# Analog_amplifer_1.net
KiCad netlist of a schematic drawn in EAGLE
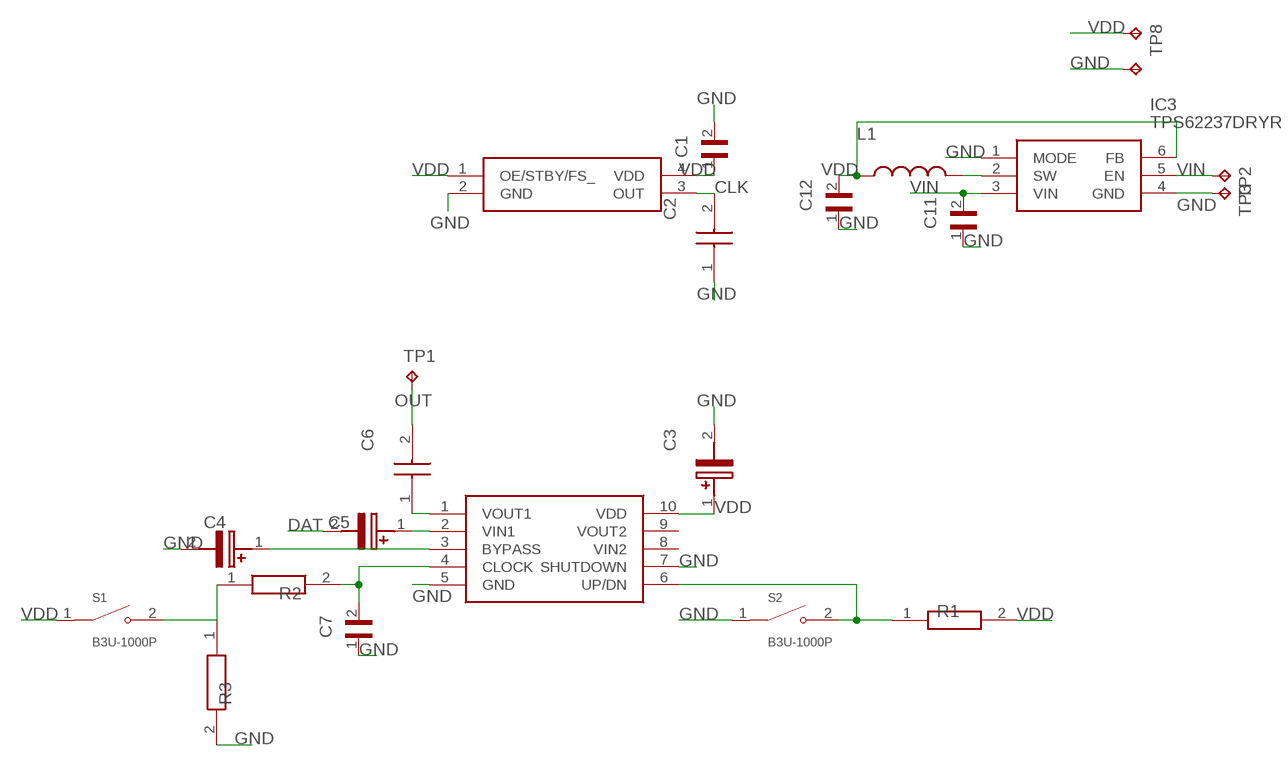
[diagram p0: schematic, sheet 1]
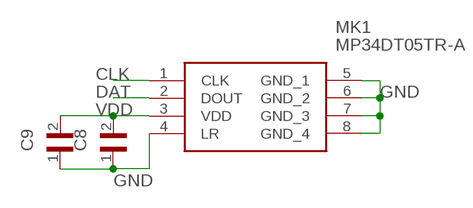
[diagram p1: schematic, sheet 2]

(export (version "E")
  (design (tool "Eeschema 10.0.6"))
  (components
    (comp (ref "C8")
      (value "JMK105C6105KV-F")
      (footprint "eagle-import:CAPC1005X55N")
      (fields (field (name "DIGI-KEY_PART_NUMBER") "587-3381-1-ND") (field (name "MF") "Taiyo Yuden"))
      (libsource (lib "eagle-import") (part "JMK105C6105KV-F"))
    )
    (comp (ref "C9")
      (value "GRM033C80J104KE15D")
      (footprint "eagle-import:CAPC0603X33N")
      (fields (field (name "DIGI-KEY_PART_NUMBER") "490-10390-1-ND") (field (name "MF") "Murata Electronics"))
      (libsource (lib "eagle-import") (part "GRM033C80J104KE15D"))
    )
    (comp (ref "MK1")
      (value "MP34DT05TR-A")
      (footprint "eagle-import:MP34DT05TRA")
      (fields (field (name "MOUSER_PART_NUMBER") "511-MP34DT05TR-A"))
      (libsource (lib "eagle-import") (part "MP34DT05TR-A"))
    )
    (comp (ref "C1")
      (value "GRM033C80J104KE15D")
      (footprint "eagle-import:CAPC0603X33N")
      (fields (field (name "DIGI-KEY_PART_NUMBER") "490-10390-1-ND") (field (name "MF") "Murata Electronics"))
      (libsource (lib "eagle-import") (part "GRM033C80J104KE15D"))
    )
    (comp (ref "C2")
      (value "GRM0115C1E5R0CE01L")
      (footprint "eagle-import:CAPC0201X14N")
      (fields (field (name "MOUSER_PART_NUMBER") "81-GRM0115C1E5RCE01L"))
      (libsource (lib "eagle-import") (part "GRM0115C1E5R0CE01L"))
    )
    (comp (ref "C3")
      (value "F380J105MUA")
      (footprint "eagle-import:CAPPC1106X60N")
      (fields (field (name "MOUSER_PART_NUMBER") "581-F380J105MUA"))
      (libsource (lib "eagle-import") (part "F380J105MUA"))
    )
    (comp (ref "C4")
      (value "F380J105MUA")
      (footprint "eagle-import:CAPPC1106X60N")
      (fields (field (name "MOUSER_PART_NUMBER") "581-F380J105MUA"))
      (libsource (lib "eagle-import") (part "F380J105MUA"))
    )
    (comp (ref "C5")
      (value "F380J105MUA")
      (footprint "eagle-import:CAPPC1106X60N")
      (fields (field (name "MOUSER_PART_NUMBER") "581-F380J105MUA"))
      (libsource (lib "eagle-import") (part "F380J105MUA"))
    )
    (comp (ref "C6")
      (value "GRM21BR60J107ME15L")
      (footprint "eagle-import:CAPC2012X145N")
      (fields (field (name "MOUSER_PART_NUMBER") "81-GRM21BR60J107ME5L"))
      (libsource (lib "eagle-import") (part "GRM21BR60J107ME15L"))
    )
    (comp (ref "C7")
      (value "GRM033C80J104KE15D")
      (footprint "eagle-import:CAPC0603X33N")
      (fields (field (name "DIGI-KEY_PART_NUMBER") "490-10390-1-ND") (field (name "MF") "Murata Electronics"))
      (libsource (lib "eagle-import") (part "GRM033C80J104KE15D"))
    )
    (comp (ref "C11")
      (value "GRM155R60J225KE95D")
      (footprint "eagle-import:CAPC1005X55N")
      (fields (field (name "DIGI-KEY_PART_NUMBER") "490-12532-1-ND") (field (name "MF") "Murata"))
      (libsource (lib "eagle-import") (part "GRM155R60J225KE95D"))
    )
    (comp (ref "C12")
      (value "GRM155R60J475ME47D")
      (footprint "eagle-import:CAPC1005X60N")
      (fields (field (name "DIGI-KEY_PART_NUMBER") "490-5915-1-ND") (field (name "MF") "Murata"))
      (libsource (lib "eagle-import") (part "GRM155R60J475ME47D"))
    )
    (comp (ref "IC1")
      (value "LM4811MM_NOPB")
      (footprint "eagle-import:SOP50P490X110-10N")
      (fields
        (field (name "ARROW_PART_NUMBER") "LM4811MM/NOPB")
        (field (name "MOUSER_PART_NUMBER") "926-LM4811MM/NOPB")
      )
      (libsource (lib "eagle-import") (part "LM4811MM_NOPB"))
    )
    (comp (ref "IC3")
      (value "TPS62237DRYR")
      (footprint "eagle-import:SON50P100X145X60-6N")
      (fields (field (name "MOUSER_PART_NUMBER") "595-TPS62237DRYR"))
      (libsource (lib "eagle-import") (part "TPS62237DRYR"))
    )
    (comp (ref "L1")
      (value "LQM21PN2R2MC0D")
      (footprint "eagle-import:INDC2012X55N")
      (fields (field (name "DIGI-KEY_PART_NUMBER") "490-4994-1-ND") (field (name "MF") "Murata"))
      (libsource (lib "eagle-import") (part "LQM21PN2R2MC0D"))
    )
    (comp (ref "R1")
      (value "RC0201FR-074K02L")
      (footprint "eagle-import:RESC0603X26N")
      (libsource (lib "eagle-import") (part "RC0201FR-074K02L"))
    )
    (comp (ref "R2")
      (value "RC0201FR-07100RL")
      (footprint "eagle-import:RESC0603X26N")
      (fields (field (name "MOUSER_PART_NUMBER") "603-RC0201FR-07100RL"))
      (libsource (lib "eagle-import") (part "RC0201FR-07100RL"))
    )
    (comp (ref "R3")
      (value "RC0201FR-07100RL")
      (footprint "eagle-import:RESC0603X26N")
      (fields (field (name "MOUSER_PART_NUMBER") "603-RC0201FR-07100RL"))
      (libsource (lib "eagle-import") (part "RC0201FR-07100RL"))
    )
    (comp (ref "S1")
      (value "B3U-1000P")
      (footprint "eagle-import:SW_B3U-1000P")
      (fields (field (name "DIGI-KEY_PART_NUMBER") "SW1020CT-ND") (field (name "MF") "Omron"))
      (libsource (lib "eagle-import") (part "B3U-1000P"))
    )
    (comp (ref "S2")
      (value "B3U-1000P")
      (footprint "eagle-import:SW_B3U-1000P")
      (fields (field (name "DIGI-KEY_PART_NUMBER") "SW1020CT-ND") (field (name "MF") "Omron"))
      (libsource (lib "eagle-import") (part "B3U-1000P"))
    )
    (comp (ref "TP1")
      (value "TPTP11R")
      (footprint "eagle-import:TP11R")
      (libsource (lib "eagle-import") (part "TPTP11R"))
    )
    (comp (ref "TP2")
      (value "TPTP11R")
      (footprint "eagle-import:TP11R")
      (libsource (lib "eagle-import") (part "TPTP11R"))
    )
    (comp (ref "TP3")
      (value "TPTP11R")
      (footprint "eagle-import:TP11R")
      (libsource (lib "eagle-import") (part "TPTP11R"))
    )
    (comp (ref "TP4")
      (value "TPTP11R")
      (footprint "eagle-import:TP11R")
      (libsource (lib "eagle-import") (part "TPTP11R"))
    )
    (comp (ref "TP8")
      (value "TPTP11R")
      (footprint "eagle-import:TP11R")
      (libsource (lib "eagle-import") (part "TPTP11R"))
    )
    (comp (ref "Y1")
      (value "DSC6053CE2A-003.0720")
      (footprint "eagle-import:DSC6053CE2A0030720")
      (libsource (lib "eagle-import") (part "DSC6053CE2A-003.0720"))
    )
  )
  (nets
    (net (code "1") (name "CLK") (class "Default")
      (node (ref "C2") (pin "2") (pinfunction "2_2") (pintype "bidirectional"))
      (node (ref "MK1") (pin "1") (pinfunction "CLK_1") (pintype "bidirectional"))
      (node (ref "Y1") (pin "3") (pinfunction "OUT_3") (pintype "bidirectional"))
    )
    (net (code "2") (name "DAT") (class "Default")
      (node (ref "C5") (pin "2") (pinfunction "-_2") (pintype "bidirectional"))
      (node (ref "MK1") (pin "2") (pinfunction "DOUT_2") (pintype "bidirectional"))
    )
    (net (code "3") (name "GND") (class "Default")
      (node (ref "C1") (pin "2") (pinfunction "2_2") (pintype "passive"))
      (node (ref "C11") (pin "1") (pinfunction "1_1") (pintype "passive"))
      (node (ref "C12") (pin "1") (pinfunction "1_1") (pintype "passive"))
      (node (ref "C2") (pin "1") (pinfunction "1_1") (pintype "bidirectional"))
      (node (ref "C3") (pin "2") (pinfunction "-_2") (pintype "bidirectional"))
      (node (ref "C4") (pin "2") (pinfunction "-_2") (pintype "bidirectional"))
      (node (ref "C7") (pin "1") (pinfunction "1_1") (pintype "passive"))
      (node (ref "C8") (pin "1") (pinfunction "1_1") (pintype "passive"))
      (node (ref "C9") (pin "1") (pinfunction "1_1") (pintype "passive"))
      (node (ref "IC1") (pin "5") (pinfunction "GND_5") (pintype "power_in"))
      (node (ref "IC1") (pin "7") (pinfunction "SHUTDOWN_7") (pintype "bidirectional"))
      (node (ref "IC3") (pin "1") (pinfunction "MODE_1") (pintype "bidirectional"))
      (node (ref "IC3") (pin "4") (pinfunction "GND_4") (pintype "bidirectional"))
      (node (ref "MK1") (pin "4") (pinfunction "LR_4") (pintype "bidirectional"))
      (node (ref "MK1") (pin "5") (pinfunction "GND_1_5") (pintype "bidirectional"))
      (node (ref "MK1") (pin "6") (pinfunction "GND_2_6") (pintype "bidirectional"))
      (node (ref "MK1") (pin "7") (pinfunction "GND_3_7") (pintype "bidirectional"))
      (node (ref "MK1") (pin "8") (pinfunction "GND_4_8") (pintype "bidirectional"))
      (node (ref "R3") (pin "2") (pinfunction "2_2") (pintype "bidirectional"))
      (node (ref "S2") (pin "1") (pinfunction "1_1") (pintype "passive"))
      (node (ref "TP3") (pin "TP") (pinfunction "TP_TP") (pintype "input"))
      (node (ref "TP4") (pin "TP") (pinfunction "TP_TP") (pintype "input"))
      (node (ref "Y1") (pin "2") (pinfunction "GND_2") (pintype "bidirectional"))
    )
    (net (code "4") (name "Net-(C4-+)") (class "Default")
      (node (ref "C4") (pin "1") (pinfunction "+_1") (pintype "bidirectional"))
      (node (ref "IC1") (pin "3") (pinfunction "BYPASS_3") (pintype "bidirectional"))
    )
    (net (code "5") (name "Net-(C5-+)") (class "Default")
      (node (ref "C5") (pin "1") (pinfunction "+_1") (pintype "bidirectional"))
      (node (ref "IC1") (pin "2") (pinfunction "VIN1_2") (pintype "input"))
    )
    (net (code "6") (name "Net-(IC1-CLOCK)") (class "Default")
      (node (ref "C7") (pin "2") (pinfunction "2_2") (pintype "passive"))
      (node (ref "IC1") (pin "4") (pinfunction "CLOCK_4") (pintype "input"))
      (node (ref "R2") (pin "2") (pinfunction "2_2") (pintype "bidirectional"))
    )
    (net (code "7") (name "Net-(IC1-UP{slash}DN)") (class "Default")
      (node (ref "IC1") (pin "6") (pinfunction "UP/DN_6") (pintype "bidirectional"))
      (node (ref "R1") (pin "1") (pinfunction "1_1") (pintype "bidirectional"))
      (node (ref "S2") (pin "2") (pinfunction "2_2") (pintype "passive"))
    )
    (net (code "8") (name "Net-(IC1-VOUT1)") (class "Default")
      (node (ref "C6") (pin "1") (pinfunction "1_1") (pintype "bidirectional"))
      (node (ref "IC1") (pin "1") (pinfunction "VOUT1_1") (pintype "output"))
    )
    (net (code "9") (name "Net-(IC3-SW)") (class "Default")
      (node (ref "IC3") (pin "2") (pinfunction "SW_2") (pintype "bidirectional"))
      (node (ref "L1") (pin "2") (pinfunction "2_2") (pintype "passive"))
    )
    (net (code "10") (name "Net-(R2-Pad1)") (class "Default")
      (node (ref "R2") (pin "1") (pinfunction "1_1") (pintype "bidirectional"))
      (node (ref "R3") (pin "1") (pinfunction "1_1") (pintype "bidirectional"))
      (node (ref "S1") (pin "2") (pinfunction "2_2") (pintype "passive"))
    )
    (net (code "11") (name "OUT") (class "Default")
      (node (ref "C6") (pin "2") (pinfunction "2_2") (pintype "bidirectional"))
      (node (ref "TP1") (pin "TP") (pinfunction "TP_TP") (pintype "input"))
    )
    (net (code "12") (name "VDD") (class "Default")
      (node (ref "C1") (pin "1") (pinfunction "1_1") (pintype "passive"))
      (node (ref "C12") (pin "2") (pinfunction "2_2") (pintype "passive"))
      (node (ref "C3") (pin "1") (pinfunction "+_1") (pintype "bidirectional"))
      (node (ref "C8") (pin "2") (pinfunction "2_2") (pintype "passive"))
      (node (ref "C9") (pin "2") (pinfunction "2_2") (pintype "passive"))
      (node (ref "IC1") (pin "10") (pinfunction "VDD_10") (pintype "power_in"))
      (node (ref "IC3") (pin "6") (pinfunction "FB_6") (pintype "bidirectional"))
      (node (ref "L1") (pin "1") (pinfunction "1_1") (pintype "passive"))
      (node (ref "MK1") (pin "3") (pinfunction "VDD_3") (pintype "bidirectional"))
      (node (ref "R1") (pin "2") (pinfunction "2_2") (pintype "bidirectional"))
      (node (ref "S1") (pin "1") (pinfunction "1_1") (pintype "passive"))
      (node (ref "TP8") (pin "TP") (pinfunction "TP_TP") (pintype "input"))
      (node (ref "Y1") (pin "1") (pinfunction "OE/STBY/FS__1") (pintype "bidirectional"))
      (node (ref "Y1") (pin "4") (pinfunction "VDD_4") (pintype "bidirectional"))
    )
    (net (code "13") (name "VIN") (class "Default")
      (node (ref "C11") (pin "2") (pinfunction "2_2") (pintype "passive"))
      (node (ref "IC3") (pin "3") (pinfunction "VIN_3") (pintype "bidirectional"))
      (node (ref "IC3") (pin "5") (pinfunction "EN_5") (pintype "bidirectional"))
      (node (ref "TP2") (pin "TP") (pinfunction "TP_TP") (pintype "input"))
    )
    (net (code "14") (name "unconnected-(IC1-VIN2-Pad8)") (class "Default")
      (node (ref "IC1") (pin "8") (pinfunction "VIN2_8") (pintype "input"))
    )
    (net (code "15") (name "unconnected-(IC1-VOUT2-Pad9)") (class "Default")
      (node (ref "IC1") (pin "9") (pinfunction "VOUT2_9") (pintype "output"))
    )
  )
)
